# SCH_f1c200-board_2024-05-28.net
KiCad netlist of a schematic drawn in EasyEDA
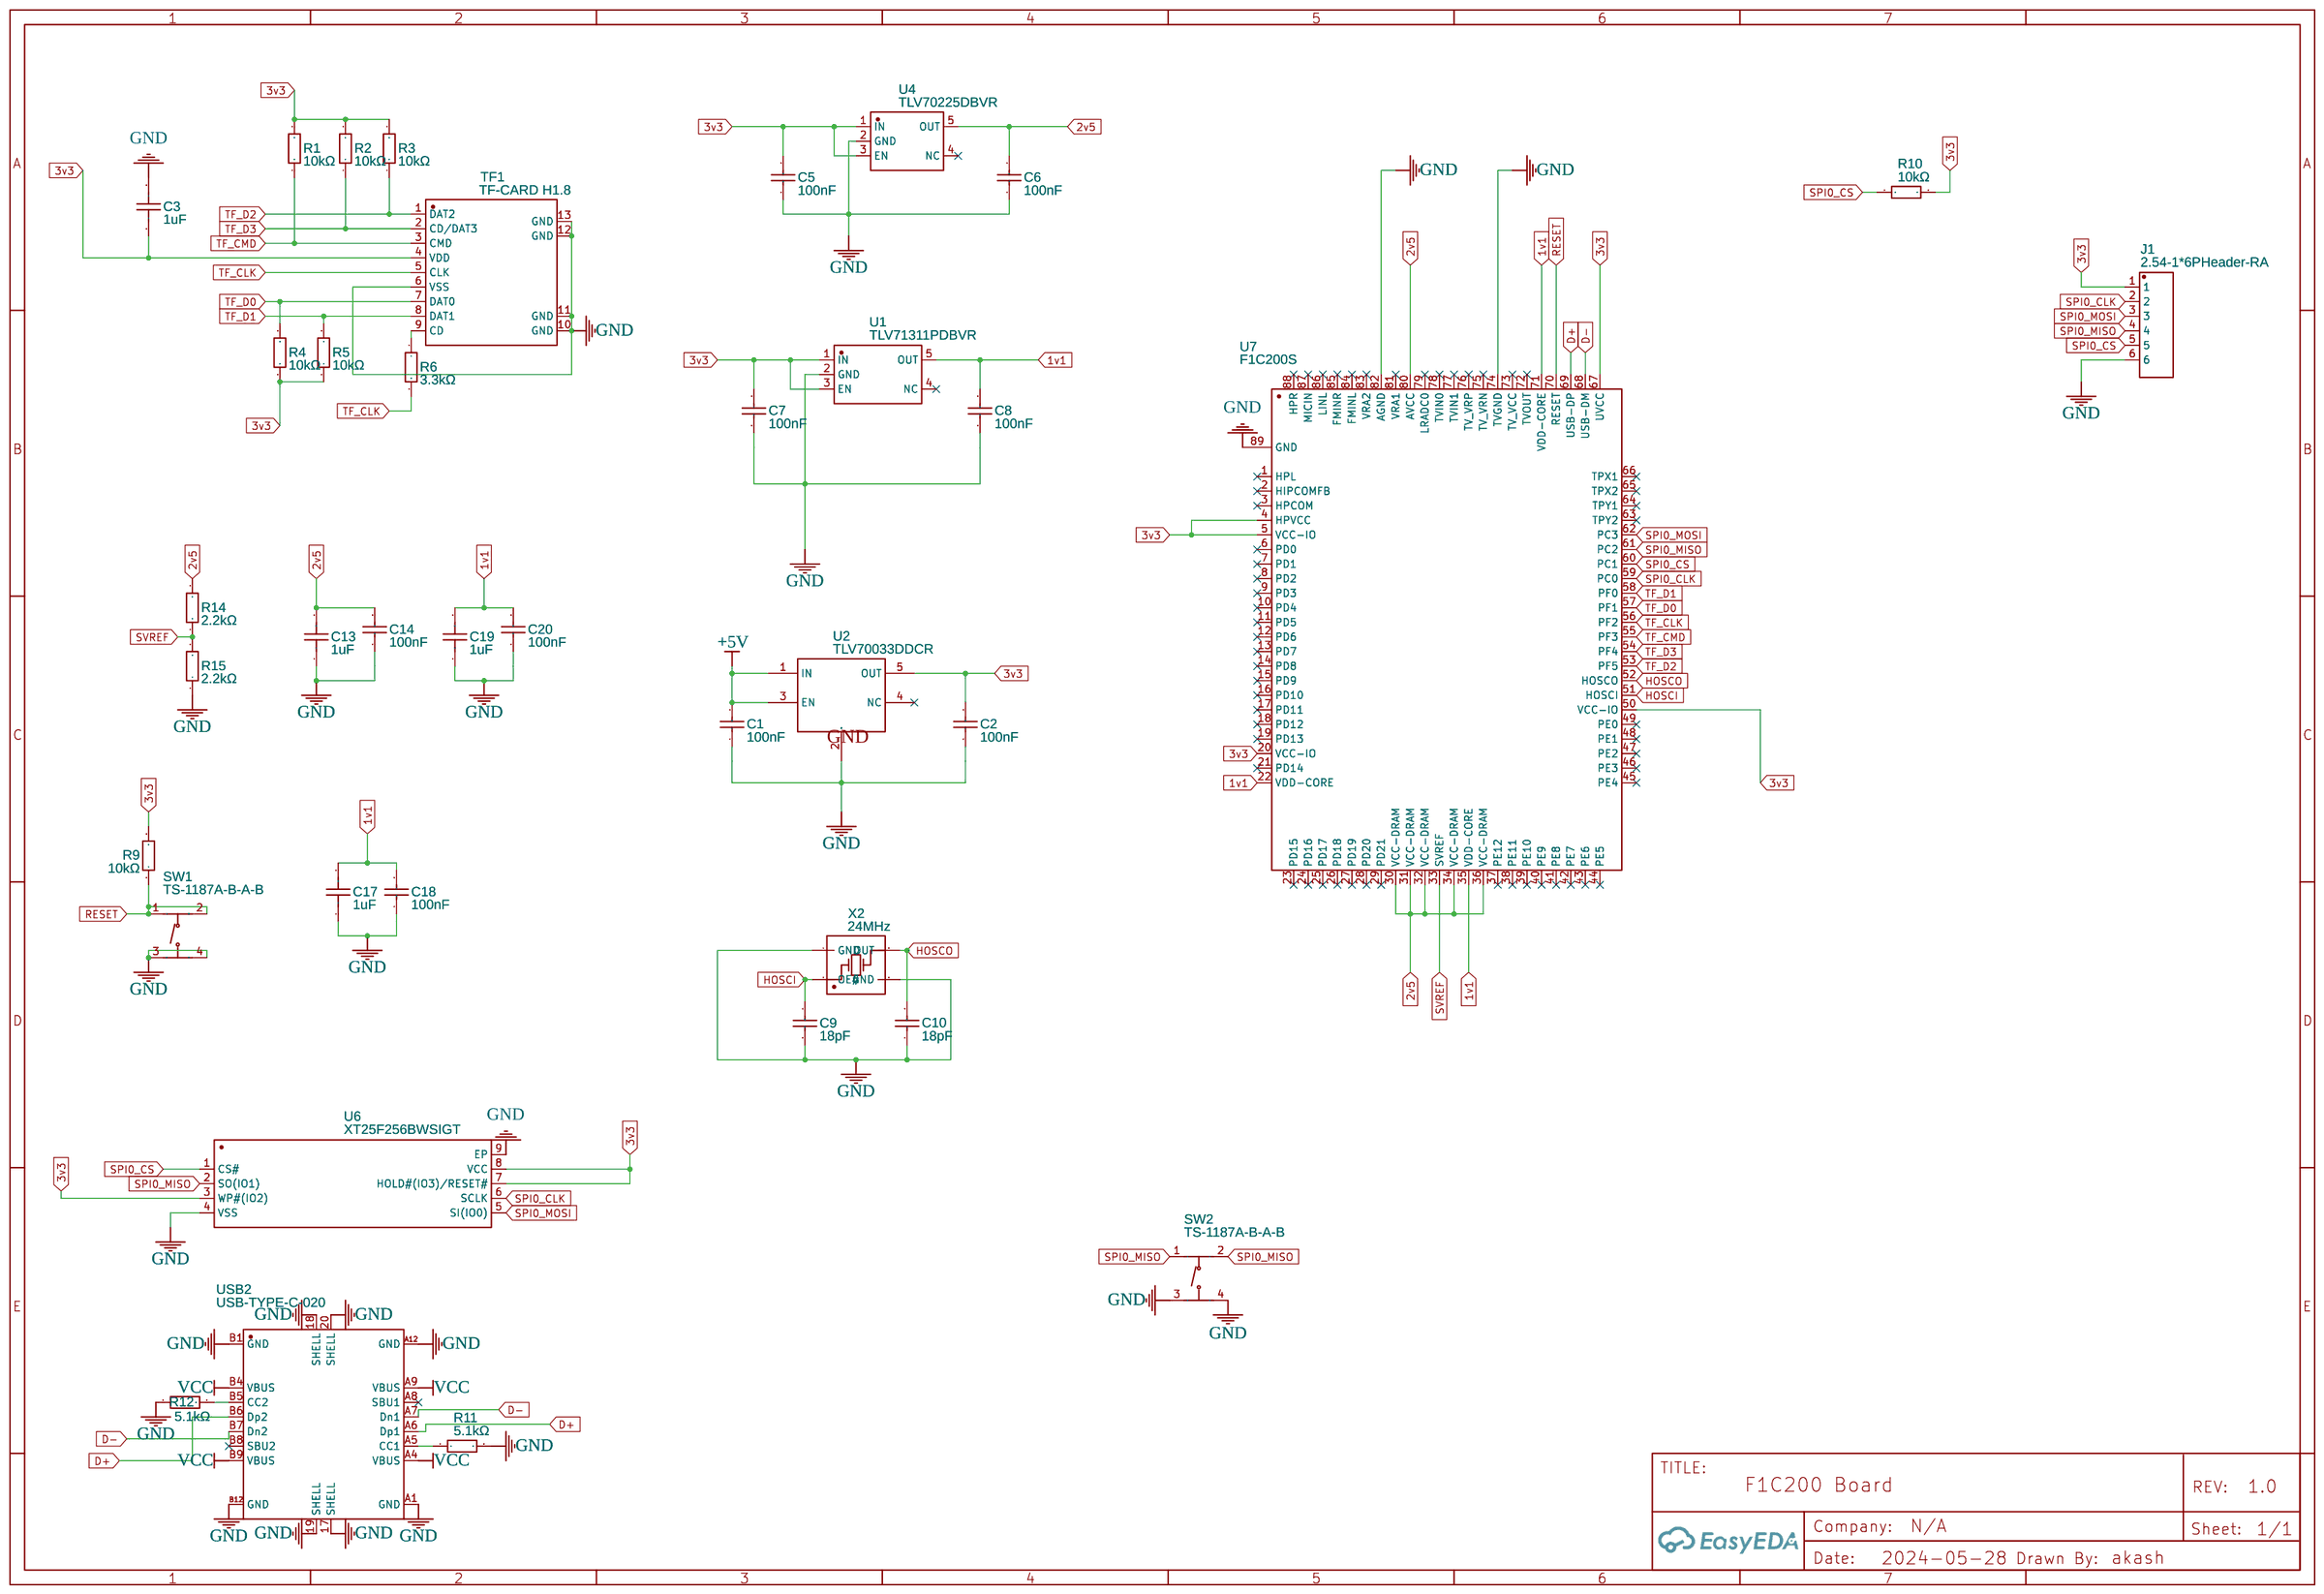
[diagram p0: schematic sheet]

(export (version "E")
  (design (tool "Eeschema 10.0.6"))
  (components
    (comp (ref "C1")
      (value "100nF")
      (fields
        (field (name "Manufacturer Part") "CL05B104KO5NNNC")
        (field (name "Manufacturer") "SAMSUNG(三星)")
      )
      (libsource (lib "") (part "CL05B104KO5NNNC"))
    )
    (comp (ref "C2")
      (value "100nF")
      (fields
        (field (name "Manufacturer Part") "CL05B104KO5NNNC")
        (field (name "Manufacturer") "SAMSUNG(三星)")
      )
      (libsource (lib "") (part "CL05B104KO5NNNC"))
    )
    (comp (ref "C3")
      (value "1uF")
      (fields
        (field (name "Manufacturer Part") "CL05A105KA5NQNC")
        (field (name "Manufacturer") "SAMSUNG(三星)")
      )
      (libsource (lib "") (part "CL05A105KA5NQNC"))
    )
    (comp (ref "C5")
      (value "100nF")
      (fields
        (field (name "Manufacturer Part") "CL05B104KO5NNNC")
        (field (name "Manufacturer") "SAMSUNG(三星)")
      )
      (libsource (lib "") (part "CL05B104KO5NNNC"))
    )
    (comp (ref "C6")
      (value "100nF")
      (fields
        (field (name "Manufacturer Part") "CL05B104KO5NNNC")
        (field (name "Manufacturer") "SAMSUNG(三星)")
      )
      (libsource (lib "") (part "CL05B104KO5NNNC"))
    )
    (comp (ref "C7")
      (value "100nF")
      (fields
        (field (name "Manufacturer Part") "CL05B104KO5NNNC")
        (field (name "Manufacturer") "SAMSUNG(三星)")
      )
      (libsource (lib "") (part "CL05B104KO5NNNC"))
    )
    (comp (ref "C8")
      (value "100nF")
      (fields
        (field (name "Manufacturer Part") "CL05B104KO5NNNC")
        (field (name "Manufacturer") "SAMSUNG(三星)")
      )
      (libsource (lib "") (part "CL05B104KO5NNNC"))
    )
    (comp (ref "C9")
      (value "18pF")
      (fields (field (name "Manufacturer Part") "0402CG180J500NT") (field (name "Manufacturer") "FH(风华)"))
      (libsource (lib "") (part "0402CG180J500NT"))
    )
    (comp (ref "C10")
      (value "18pF")
      (fields (field (name "Manufacturer Part") "0402CG180J500NT") (field (name "Manufacturer") "FH(风华)"))
      (libsource (lib "") (part "0402CG180J500NT"))
    )
    (comp (ref "C13")
      (value "1uF")
      (fields
        (field (name "Manufacturer Part") "CL05A105KA5NQNC")
        (field (name "Manufacturer") "SAMSUNG(三星)")
      )
      (libsource (lib "") (part "CL05A105KA5NQNC"))
    )
    (comp (ref "C14")
      (value "100nF")
      (fields
        (field (name "Manufacturer Part") "CL05B104KO5NNNC")
        (field (name "Manufacturer") "SAMSUNG(三星)")
      )
      (libsource (lib "") (part "CL05B104KO5NNNC"))
    )
    (comp (ref "C17")
      (value "1uF")
      (fields
        (field (name "Manufacturer Part") "CL05A105KA5NQNC")
        (field (name "Manufacturer") "SAMSUNG(三星)")
      )
      (libsource (lib "") (part "CL05A105KA5NQNC"))
    )
    (comp (ref "C18")
      (value "100nF")
      (fields
        (field (name "Manufacturer Part") "CL05B104KO5NNNC")
        (field (name "Manufacturer") "SAMSUNG(三星)")
      )
      (libsource (lib "") (part "CL05B104KO5NNNC"))
    )
    (comp (ref "C19")
      (value "1uF")
      (fields
        (field (name "Manufacturer Part") "CL05A105KA5NQNC")
        (field (name "Manufacturer") "SAMSUNG(三星)")
      )
      (libsource (lib "") (part "CL05A105KA5NQNC"))
    )
    (comp (ref "C20")
      (value "100nF")
      (fields
        (field (name "Manufacturer Part") "CL05B104KO5NNNC")
        (field (name "Manufacturer") "SAMSUNG(三星)")
      )
      (libsource (lib "") (part "CL05B104KO5NNNC"))
    )
    (comp (ref "J1")
      (value "2.54-1*6PHeader-RA")
      (fields
        (field (name "Manufacturer Part") "2.54-1*6P反弯排针")
        (field (name "Manufacturer") "BOOMELE(博穆精密)")
      )
      (libsource (lib "") (part "2.54-1*6PHeader-RA"))
    )
    (comp (ref "R1")
      (value "10kΩ")
      (fields
        (field (name "Manufacturer Part") "0603WAF1002T5E")
        (field (name "Manufacturer") "UNI-ROYAL(厚声)")
      )
      (libsource (lib "") (part "0603WAF1002T5E"))
    )
    (comp (ref "R2")
      (value "10kΩ")
      (fields
        (field (name "Manufacturer Part") "0603WAF1002T5E")
        (field (name "Manufacturer") "UNI-ROYAL(厚声)")
      )
      (libsource (lib "") (part "0603WAF1002T5E"))
    )
    (comp (ref "R3")
      (value "10kΩ")
      (fields
        (field (name "Manufacturer Part") "0603WAF1002T5E")
        (field (name "Manufacturer") "UNI-ROYAL(厚声)")
      )
      (libsource (lib "") (part "0603WAF1002T5E"))
    )
    (comp (ref "R4")
      (value "10kΩ")
      (fields
        (field (name "Manufacturer Part") "0603WAF1002T5E")
        (field (name "Manufacturer") "UNI-ROYAL(厚声)")
      )
      (libsource (lib "") (part "0603WAF1002T5E"))
    )
    (comp (ref "R5")
      (value "10kΩ")
      (fields
        (field (name "Manufacturer Part") "0603WAF1002T5E")
        (field (name "Manufacturer") "UNI-ROYAL(厚声)")
      )
      (libsource (lib "") (part "0603WAF1002T5E"))
    )
    (comp (ref "R6")
      (value "3.3kΩ")
      (fields
        (field (name "Manufacturer Part") "0603WAF3301T5E")
        (field (name "Manufacturer") "UNI-ROYAL(厚声)")
      )
      (libsource (lib "") (part "0603WAF3301T5E"))
    )
    (comp (ref "R9")
      (value "10kΩ")
      (fields
        (field (name "Manufacturer Part") "0603WAF1002T5E")
        (field (name "Manufacturer") "UNI-ROYAL(厚声)")
      )
      (libsource (lib "") (part "0603WAF1002T5E"))
    )
    (comp (ref "R10")
      (value "10kΩ")
      (fields
        (field (name "Manufacturer Part") "0603WAF1002T5E")
        (field (name "Manufacturer") "UNI-ROYAL(厚声)")
      )
      (libsource (lib "") (part "0603WAF1002T5E_1"))
    )
    (comp (ref "R11")
      (value "5.1kΩ")
      (fields
        (field (name "Manufacturer Part") "0402WGF5101TCE")
        (field (name "Manufacturer") "UNI-ROYAL(厚声)")
      )
      (libsource (lib "") (part "0402WGF5101TCE"))
    )
    (comp (ref "R12")
      (value "5.1kΩ")
      (fields
        (field (name "Manufacturer Part") "0402WGF5101TCE")
        (field (name "Manufacturer") "UNI-ROYAL(厚声)")
      )
      (libsource (lib "") (part "0402WGF5101TCE"))
    )
    (comp (ref "R14")
      (value "2.2kΩ")
      (fields
        (field (name "Manufacturer Part") "0603WAF2201T5E")
        (field (name "Manufacturer") "UNI-ROYAL(厚声)")
      )
      (libsource (lib "") (part "0603WAF2201T5E"))
    )
    (comp (ref "R15")
      (value "2.2kΩ")
      (fields
        (field (name "Manufacturer Part") "0603WAF2201T5E")
        (field (name "Manufacturer") "UNI-ROYAL(厚声)")
      )
      (libsource (lib "") (part "0603WAF2201T5E"))
    )
    (comp (ref "SW1")
      (value "TS-1187A-B-A-B")
      (fields (field (name "Manufacturer") "XKB Connectivity(中国星坤)"))
      (libsource (lib "") (part "TS-1187A-B-A-B"))
    )
    (comp (ref "SW2")
      (value "TS-1187A-B-A-B")
      (fields (field (name "Manufacturer") "XKB Connectivity(中国星坤)"))
      (libsource (lib "") (part "TS-1187A-B-A-B"))
    )
    (comp (ref "TF1")
      (value "TF-CARD H1.8")
      (fields (field (name "Manufacturer") "SHOU HAN(首韩)"))
      (libsource (lib "") (part "TF-CARD H1.8"))
    )
    (comp (ref "U1")
      (value "TLV71311PDBVR")
      (fields (field (name "Manufacturer") "TI(德州仪器)"))
      (libsource (lib "") (part "TLV71311PDBVR"))
    )
    (comp (ref "U2")
      (value "TLV70033DDCR")
      (fields (field (name "Manufacturer") "TI(德州仪器)"))
      (libsource (lib "") (part "TLV70033DDCR"))
    )
    (comp (ref "U4")
      (value "TLV70225DBVR")
      (fields (field (name "Manufacturer") "TI(德州仪器)"))
      (libsource (lib "") (part "TLV70225DBVR"))
    )
    (comp (ref "U6")
      (value "XT25F256BWSIGT")
      (fields (field (name "Manufacturer") "XTX(芯天下)"))
      (libsource (lib "") (part "XT25F256BWSIGT"))
    )
    (comp (ref "U7")
      (value "F1C200S")
      (fields (field (name "Manufacturer") "Allwinner(全志)"))
      (libsource (lib "") (part "F1C200S"))
    )
    (comp (ref "USB2")
      (value "USB-TYPE-C-020")
      (fields (field (name "Manufacturer") "DEALON(德艺隆)"))
      (libsource (lib "") (part "USB-TYPE-C-020"))
    )
    (comp (ref "X2")
      (value "24MHz")
      (fields (field (name "Manufacturer Part") "7U24000E12UCG") (field (name "Manufacturer") "SJK(晶科鑫)"))
      (libsource (lib "") (part "7U24000E12UCG"))
    )
  )
  (nets
    (net (code "1") (name "+5V") (class "Default")
      (node (ref "C1") (pin "2") (pinfunction "2_2") (pintype "input"))
      (node (ref "U2") (pin "1") (pinfunction "IN_1") (pintype "passive"))
      (node (ref "U2") (pin "3") (pinfunction "EN_3") (pintype "unspecified"))
    )
    (net (code "2") (name "1v1") (class "Default")
      (node (ref "C17") (pin "2") (pinfunction "2_2") (pintype "unspecified"))
      (node (ref "C18") (pin "2") (pinfunction "2_2") (pintype "input"))
      (node (ref "C19") (pin "2") (pinfunction "2_2") (pintype "unspecified"))
      (node (ref "C20") (pin "2") (pinfunction "2_2") (pintype "input"))
      (node (ref "C8") (pin "2") (pinfunction "2_2") (pintype "input"))
      (node (ref "U1") (pin "5") (pinfunction "OUT_5") (pintype "unspecified"))
      (node (ref "U7") (pin "22") (pinfunction "VDD-CORE_22") (pintype "unspecified"))
      (node (ref "U7") (pin "35") (pinfunction "VDD-CORE_35") (pintype "unspecified"))
      (node (ref "U7") (pin "71") (pinfunction "VDD-CORE_71") (pintype "unspecified"))
    )
    (net (code "3") (name "2v5") (class "Default")
      (node (ref "C13") (pin "2") (pinfunction "2_2") (pintype "unspecified"))
      (node (ref "C14") (pin "2") (pinfunction "2_2") (pintype "input"))
      (node (ref "C6") (pin "2") (pinfunction "2_2") (pintype "input"))
      (node (ref "R14") (pin "2") (pinfunction "2_2") (pintype "input"))
      (node (ref "U4") (pin "5") (pinfunction "OUT_5") (pintype "unspecified"))
      (node (ref "U7") (pin "30") (pinfunction "VCC-DRAM_30") (pintype "unspecified"))
      (node (ref "U7") (pin "31") (pinfunction "VCC-DRAM_31") (pintype "unspecified"))
      (node (ref "U7") (pin "32") (pinfunction "VCC-DRAM_32") (pintype "unspecified"))
      (node (ref "U7") (pin "34") (pinfunction "VCC-DRAM_34") (pintype "unspecified"))
      (node (ref "U7") (pin "36") (pinfunction "VCC-DRAM_36") (pintype "unspecified"))
      (node (ref "U7") (pin "80") (pinfunction "AVCC_80") (pintype "unspecified"))
    )
    (net (code "4") (name "3v3") (class "Default")
      (node (ref "C2") (pin "2") (pinfunction "2_2") (pintype "input"))
      (node (ref "C3") (pin "1") (pinfunction "1_1") (pintype "unspecified"))
      (node (ref "C5") (pin "2") (pinfunction "2_2") (pintype "input"))
      (node (ref "C7") (pin "2") (pinfunction "2_2") (pintype "input"))
      (node (ref "J1") (pin "1") (pinfunction "1_1") (pintype "unspecified"))
      (node (ref "R1") (pin "2") (pinfunction "2_2") (pintype "input"))
      (node (ref "R10") (pin "2") (pinfunction "2_2") (pintype "input"))
      (node (ref "R2") (pin "2") (pinfunction "2_2") (pintype "input"))
      (node (ref "R3") (pin "2") (pinfunction "2_2") (pintype "input"))
      (node (ref "R4") (pin "1") (pinfunction "1_1") (pintype "input"))
      (node (ref "R5") (pin "1") (pinfunction "1_1") (pintype "input"))
      (node (ref "R9") (pin "2") (pinfunction "2_2") (pintype "input"))
      (node (ref "TF1") (pin "4") (pinfunction "VDD_4") (pintype "unspecified"))
      (node (ref "U1") (pin "1") (pinfunction "IN_1") (pintype "unspecified"))
      (node (ref "U1") (pin "3") (pinfunction "EN_3") (pintype "unspecified"))
      (node (ref "U2") (pin "5") (pinfunction "OUT_5") (pintype "passive"))
      (node (ref "U4") (pin "1") (pinfunction "IN_1") (pintype "unspecified"))
      (node (ref "U4") (pin "3") (pinfunction "EN_3") (pintype "unspecified"))
      (node (ref "U6") (pin "3") (pinfunction "WP#(IO2)_3") (pintype "unspecified"))
      (node (ref "U6") (pin "7") (pinfunction "HOLD#(IO3)/RESET#_7") (pintype "unspecified"))
      (node (ref "U6") (pin "8") (pinfunction "VCC_8") (pintype "unspecified"))
      (node (ref "U7") (pin "20") (pinfunction "VCC-IO_20") (pintype "unspecified"))
      (node (ref "U7") (pin "4") (pinfunction "HPVCC_4") (pintype "unspecified"))
      (node (ref "U7") (pin "5") (pinfunction "VCC-IO_5") (pintype "unspecified"))
      (node (ref "U7") (pin "50") (pinfunction "VCC-IO_50") (pintype "unspecified"))
      (node (ref "U7") (pin "67") (pinfunction "UVCC_67") (pintype "unspecified"))
    )
    (net (code "5") (name "D+") (class "Default")
      (node (ref "U7") (pin "69") (pinfunction "USB-DP_69") (pintype "unspecified"))
      (node (ref "USB2") (pin "A6") (pinfunction "Dp1_A6") (pintype "unspecified"))
      (node (ref "USB2") (pin "B6") (pinfunction "Dp2_B6") (pintype "unspecified"))
    )
    (net (code "6") (name "D-") (class "Default")
      (node (ref "U7") (pin "68") (pinfunction "USB-DM_68") (pintype "unspecified"))
      (node (ref "USB2") (pin "A7") (pinfunction "Dn1_A7") (pintype "unspecified"))
      (node (ref "USB2") (pin "B7") (pinfunction "Dn2_B7") (pintype "unspecified"))
    )
    (net (code "7") (name "GND") (class "Default")
      (node (ref "C1") (pin "1") (pinfunction "1_1") (pintype "input"))
      (node (ref "C10") (pin "1") (pinfunction "1_1") (pintype "input"))
      (node (ref "C13") (pin "1") (pinfunction "1_1") (pintype "unspecified"))
      (node (ref "C14") (pin "1") (pinfunction "1_1") (pintype "input"))
      (node (ref "C17") (pin "1") (pinfunction "1_1") (pintype "unspecified"))
      (node (ref "C18") (pin "1") (pinfunction "1_1") (pintype "input"))
      (node (ref "C19") (pin "1") (pinfunction "1_1") (pintype "unspecified"))
      (node (ref "C2") (pin "1") (pinfunction "1_1") (pintype "input"))
      (node (ref "C20") (pin "1") (pinfunction "1_1") (pintype "input"))
      (node (ref "C3") (pin "2") (pinfunction "2_2") (pintype "unspecified"))
      (node (ref "C5") (pin "1") (pinfunction "1_1") (pintype "input"))
      (node (ref "C6") (pin "1") (pinfunction "1_1") (pintype "input"))
      (node (ref "C7") (pin "1") (pinfunction "1_1") (pintype "input"))
      (node (ref "C8") (pin "1") (pinfunction "1_1") (pintype "input"))
      (node (ref "C9") (pin "1") (pinfunction "1_1") (pintype "input"))
      (node (ref "J1") (pin "6") (pinfunction "6_6") (pintype "unspecified"))
      (node (ref "R11") (pin "2") (pinfunction "2_2") (pintype "input"))
      (node (ref "R12") (pin "1") (pinfunction "1_1") (pintype "input"))
      (node (ref "R15") (pin "1") (pinfunction "1_1") (pintype "input"))
      (node (ref "SW1") (pin "3") (pinfunction "C_3") (pintype "unspecified"))
      (node (ref "SW1") (pin "4") (pinfunction "D_4") (pintype "unspecified"))
      (node (ref "SW2") (pin "3") (pinfunction "C_3") (pintype "unspecified"))
      (node (ref "SW2") (pin "4") (pinfunction "D_4") (pintype "unspecified"))
      (node (ref "TF1") (pin "10") (pinfunction "GND_10") (pintype "unspecified"))
      (node (ref "TF1") (pin "11") (pinfunction "GND_11") (pintype "unspecified"))
      (node (ref "TF1") (pin "12") (pinfunction "GND_12") (pintype "unspecified"))
      (node (ref "TF1") (pin "13") (pinfunction "GND_13") (pintype "unspecified"))
      (node (ref "TF1") (pin "6") (pinfunction "VSS_6") (pintype "unspecified"))
      (node (ref "U1") (pin "2") (pinfunction "GND_2") (pintype "unspecified"))
      (node (ref "U2") (pin "2") (pinfunction "GND_2") (pintype "passive"))
      (node (ref "U4") (pin "2") (pinfunction "GND_2") (pintype "unspecified"))
      (node (ref "U6") (pin "4") (pinfunction "VSS_4") (pintype "unspecified"))
      (node (ref "U6") (pin "9") (pinfunction "EP_9") (pintype "unspecified"))
      (node (ref "U7") (pin "74") (pinfunction "TVGND_74") (pintype "unspecified"))
      (node (ref "U7") (pin "82") (pinfunction "AGND_82") (pintype "unspecified"))
      (node (ref "U7") (pin "89") (pinfunction "GND_89") (pintype "unspecified"))
      (node (ref "USB2") (pin "17") (pinfunction "SHELL_17") (pintype "unspecified"))
      (node (ref "USB2") (pin "18") (pinfunction "SHELL_18") (pintype "unspecified"))
      (node (ref "USB2") (pin "19") (pinfunction "SHELL_19") (pintype "unspecified"))
      (node (ref "USB2") (pin "20") (pinfunction "SHELL_20") (pintype "unspecified"))
      (node (ref "USB2") (pin "A1") (pinfunction "GND_A1") (pintype "unspecified"))
      (node (ref "USB2") (pin "A12") (pinfunction "GND_A12") (pintype "unspecified"))
      (node (ref "USB2") (pin "B1") (pinfunction "GND_B1") (pintype "unspecified"))
      (node (ref "USB2") (pin "B12") (pinfunction "GND_B12") (pintype "unspecified"))
      (node (ref "X2") (pin "2") (pinfunction "GND_2") (pintype "input"))
      (node (ref "X2") (pin "4") (pinfunction "GND_4") (pintype "input"))
    )
    (net (code "8") (name "HOSCI") (class "Default")
      (node (ref "C9") (pin "2") (pinfunction "2_2") (pintype "input"))
      (node (ref "U7") (pin "51") (pinfunction "HOSCI_51") (pintype "unspecified"))
      (node (ref "X2") (pin "1") (pinfunction "OE#_1") (pintype "input"))
    )
    (net (code "9") (name "HOSCO") (class "Default")
      (node (ref "C10") (pin "2") (pinfunction "2_2") (pintype "input"))
      (node (ref "U7") (pin "52") (pinfunction "HOSCO_52") (pintype "unspecified"))
      (node (ref "X2") (pin "3") (pinfunction "OUT_3") (pintype "input"))
    )
    (net (code "10") (name "Net-(TF1-CD)") (class "Default")
      (node (ref "R6") (pin "1") (pinfunction "1_1") (pintype "input"))
      (node (ref "TF1") (pin "9") (pinfunction "CD_9") (pintype "unspecified"))
    )
    (net (code "11") (name "Net-(USB2-CC1)") (class "Default")
      (node (ref "R11") (pin "1") (pinfunction "1_1") (pintype "input"))
      (node (ref "USB2") (pin "A5") (pinfunction "CC1_A5") (pintype "unspecified"))
    )
    (net (code "12") (name "Net-(USB2-CC2)") (class "Default")
      (node (ref "R12") (pin "2") (pinfunction "2_2") (pintype "input"))
      (node (ref "USB2") (pin "B5") (pinfunction "CC2_B5") (pintype "unspecified"))
    )
    (net (code "13") (name "RESET") (class "Default")
      (node (ref "R9") (pin "1") (pinfunction "1_1") (pintype "input"))
      (node (ref "SW1") (pin "1") (pinfunction "A_1") (pintype "unspecified"))
      (node (ref "SW1") (pin "2") (pinfunction "B_2") (pintype "unspecified"))
      (node (ref "U7") (pin "70") (pinfunction "RESET_70") (pintype "unspecified"))
    )
    (net (code "14") (name "SPI0_CLK") (class "Default")
      (node (ref "J1") (pin "2") (pinfunction "2_2") (pintype "unspecified"))
      (node (ref "U6") (pin "6") (pinfunction "SCLK_6") (pintype "unspecified"))
      (node (ref "U7") (pin "59") (pinfunction "PC0_59") (pintype "unspecified"))
    )
    (net (code "15") (name "SPI0_CS") (class "Default")
      (node (ref "J1") (pin "5") (pinfunction "5_5") (pintype "unspecified"))
      (node (ref "R10") (pin "1") (pinfunction "1_1") (pintype "input"))
      (node (ref "U6") (pin "1") (pinfunction "CS#_1") (pintype "unspecified"))
      (node (ref "U7") (pin "60") (pinfunction "PC1_60") (pintype "unspecified"))
    )
    (net (code "16") (name "SPI0_MISO") (class "Default")
      (node (ref "J1") (pin "4") (pinfunction "4_4") (pintype "unspecified"))
      (node (ref "SW2") (pin "1") (pinfunction "A_1") (pintype "unspecified"))
      (node (ref "SW2") (pin "2") (pinfunction "B_2") (pintype "unspecified"))
      (node (ref "U6") (pin "2") (pinfunction "SO(IO1)_2") (pintype "unspecified"))
      (node (ref "U7") (pin "61") (pinfunction "PC2_61") (pintype "unspecified"))
    )
    (net (code "17") (name "SPI0_MOSI") (class "Default")
      (node (ref "J1") (pin "3") (pinfunction "3_3") (pintype "unspecified"))
      (node (ref "U6") (pin "5") (pinfunction "SI(IO0)_5") (pintype "unspecified"))
      (node (ref "U7") (pin "62") (pinfunction "PC3_62") (pintype "unspecified"))
    )
    (net (code "18") (name "SVREF") (class "Default")
      (node (ref "R14") (pin "1") (pinfunction "1_1") (pintype "input"))
      (node (ref "R15") (pin "2") (pinfunction "2_2") (pintype "input"))
      (node (ref "U7") (pin "33") (pinfunction "SVREF_33") (pintype "unspecified"))
    )
    (net (code "19") (name "TF_CLK") (class "Default")
      (node (ref "R6") (pin "2") (pinfunction "2_2") (pintype "input"))
      (node (ref "TF1") (pin "5") (pinfunction "CLK_5") (pintype "unspecified"))
      (node (ref "U7") (pin "56") (pinfunction "PF2_56") (pintype "unspecified"))
    )
    (net (code "20") (name "TF_CMD") (class "Default")
      (node (ref "R1") (pin "1") (pinfunction "1_1") (pintype "input"))
      (node (ref "TF1") (pin "3") (pinfunction "CMD_3") (pintype "unspecified"))
      (node (ref "U7") (pin "55") (pinfunction "PF3_55") (pintype "unspecified"))
    )
    (net (code "21") (name "TF_D0") (class "Default")
      (node (ref "R4") (pin "2") (pinfunction "2_2") (pintype "input"))
      (node (ref "TF1") (pin "7") (pinfunction "DAT0_7") (pintype "unspecified"))
      (node (ref "U7") (pin "57") (pinfunction "PF1_57") (pintype "unspecified"))
    )
    (net (code "22") (name "TF_D1") (class "Default")
      (node (ref "R5") (pin "2") (pinfunction "2_2") (pintype "input"))
      (node (ref "TF1") (pin "8") (pinfunction "DAT1_8") (pintype "unspecified"))
      (node (ref "U7") (pin "58") (pinfunction "PF0_58") (pintype "unspecified"))
    )
    (net (code "23") (name "TF_D2") (class "Default")
      (node (ref "R3") (pin "1") (pinfunction "1_1") (pintype "input"))
      (node (ref "TF1") (pin "1") (pinfunction "DAT2_1") (pintype "unspecified"))
      (node (ref "U7") (pin "53") (pinfunction "PF5_53") (pintype "unspecified"))
    )
    (net (code "24") (name "TF_D3") (class "Default")
      (node (ref "R2") (pin "1") (pinfunction "1_1") (pintype "input"))
      (node (ref "TF1") (pin "2") (pinfunction "CD/DAT3_2") (pintype "unspecified"))
      (node (ref "U7") (pin "54") (pinfunction "PF4_54") (pintype "unspecified"))
    )
    (net (code "25") (name "VCC") (class "Default")
      (node (ref "USB2") (pin "A4") (pinfunction "VBUS_A4") (pintype "unspecified"))
      (node (ref "USB2") (pin "A9") (pinfunction "VBUS_A9") (pintype "unspecified"))
      (node (ref "USB2") (pin "B4") (pinfunction "VBUS_B4") (pintype "unspecified"))
      (node (ref "USB2") (pin "B9") (pinfunction "VBUS_B9") (pintype "unspecified"))
    )
    (net (code "26") (name "unconnected-(U1-NC-Pad4)") (class "Default")
      (node (ref "U1") (pin "4") (pinfunction "NC_4") (pintype "unspecified+no_connect"))
    )
    (net (code "27") (name "unconnected-(U2-NC-Pad4)") (class "Default")
      (node (ref "U2") (pin "4") (pinfunction "NC_4") (pintype "unspecified+no_connect"))
    )
    (net (code "28") (name "unconnected-(U4-NC-Pad4)") (class "Default")
      (node (ref "U4") (pin "4") (pinfunction "NC_4") (pintype "unspecified+no_connect"))
    )
    (net (code "29") (name "unconnected-(U7-FMINL-Pad84)") (class "Default")
      (node (ref "U7") (pin "84") (pinfunction "FMINL_84") (pintype "unspecified+no_connect"))
    )
    (net (code "30") (name "unconnected-(U7-FMINR-Pad85)") (class "Default")
      (node (ref "U7") (pin "85") (pinfunction "FMINR_85") (pintype "unspecified+no_connect"))
    )
    (net (code "31") (name "unconnected-(U7-HIPCOMFB-Pad2)") (class "Default")
      (node (ref "U7") (pin "2") (pinfunction "HIPCOMFB_2") (pintype "unspecified+no_connect"))
    )
    (net (code "32") (name "unconnected-(U7-HPCOM-Pad3)") (class "Default")
      (node (ref "U7") (pin "3") (pinfunction "HPCOM_3") (pintype "unspecified+no_connect"))
    )
    (net (code "33") (name "unconnected-(U7-HPL-Pad1)") (class "Default")
      (node (ref "U7") (pin "1") (pinfunction "HPL_1") (pintype "unspecified+no_connect"))
    )
    (net (code "34") (name "unconnected-(U7-HPR-Pad88)") (class "Default")
      (node (ref "U7") (pin "88") (pinfunction "HPR_88") (pintype "unspecified+no_connect"))
    )
    (net (code "35") (name "unconnected-(U7-LINL-Pad86)") (class "Default")
      (node (ref "U7") (pin "86") (pinfunction "LINL_86") (pintype "unspecified+no_connect"))
    )
    (net (code "36") (name "unconnected-(U7-LRADC0-Pad79)") (class "Default")
      (node (ref "U7") (pin "79") (pinfunction "LRADC0_79") (pintype "unspecified+no_connect"))
    )
    (net (code "37") (name "unconnected-(U7-MICIN-Pad87)") (class "Default")
      (node (ref "U7") (pin "87") (pinfunction "MICIN_87") (pintype "unspecified+no_connect"))
    )
    (net (code "38") (name "unconnected-(U7-PD0-Pad6)") (class "Default")
      (node (ref "U7") (pin "6") (pinfunction "PD0_6") (pintype "unspecified+no_connect"))
    )
    (net (code "39") (name "unconnected-(U7-PD1-Pad7)") (class "Default")
      (node (ref "U7") (pin "7") (pinfunction "PD1_7") (pintype "unspecified+no_connect"))
    )
    (net (code "40") (name "unconnected-(U7-PD2-Pad8)") (class "Default")
      (node (ref "U7") (pin "8") (pinfunction "PD2_8") (pintype "unspecified+no_connect"))
    )
    (net (code "41") (name "unconnected-(U7-PD3-Pad9)") (class "Default")
      (node (ref "U7") (pin "9") (pinfunction "PD3_9") (pintype "unspecified+no_connect"))
    )
    (net (code "42") (name "unconnected-(U7-PD4-Pad10)") (class "Default")
      (node (ref "U7") (pin "10") (pinfunction "PD4_10") (pintype "unspecified+no_connect"))
    )
    (net (code "43") (name "unconnected-(U7-PD5-Pad11)") (class "Default")
      (node (ref "U7") (pin "11") (pinfunction "PD5_11") (pintype "unspecified+no_connect"))
    )
    (net (code "44") (name "unconnected-(U7-PD6-Pad12)") (class "Default")
      (node (ref "U7") (pin "12") (pinfunction "PD6_12") (pintype "unspecified+no_connect"))
    )
    (net (code "45") (name "unconnected-(U7-PD7-Pad13)") (class "Default")
      (node (ref "U7") (pin "13") (pinfunction "PD7_13") (pintype "unspecified+no_connect"))
    )
    (net (code "46") (name "unconnected-(U7-PD8-Pad14)") (class "Default")
      (node (ref "U7") (pin "14") (pinfunction "PD8_14") (pintype "unspecified+no_connect"))
    )
    (net (code "47") (name "unconnected-(U7-PD9-Pad15)") (class "Default")
      (node (ref "U7") (pin "15") (pinfunction "PD9_15") (pintype "unspecified+no_connect"))
    )
    (net (code "48") (name "unconnected-(U7-PD10-Pad16)") (class "Default")
      (node (ref "U7") (pin "16") (pinfunction "PD10_16") (pintype "unspecified+no_connect"))
    )
    (net (code "49") (name "unconnected-(U7-PD11-Pad17)") (class "Default")
      (node (ref "U7") (pin "17") (pinfunction "PD11_17") (pintype "unspecified+no_connect"))
    )
    (net (code "50") (name "unconnected-(U7-PD12-Pad18)") (class "Default")
      (node (ref "U7") (pin "18") (pinfunction "PD12_18") (pintype "unspecified+no_connect"))
    )
    (net (code "51") (name "unconnected-(U7-PD13-Pad19)") (class "Default")
      (node (ref "U7") (pin "19") (pinfunction "PD13_19") (pintype "unspecified+no_connect"))
    )
    (net (code "52") (name "unconnected-(U7-PD14-Pad21)") (class "Default")
      (node (ref "U7") (pin "21") (pinfunction "PD14_21") (pintype "unspecified+no_connect"))
    )
    (net (code "53") (name "unconnected-(U7-PD15-Pad23)") (class "Default")
      (node (ref "U7") (pin "23") (pinfunction "PD15_23") (pintype "unspecified+no_connect"))
    )
    (net (code "54") (name "unconnected-(U7-PD16-Pad24)") (class "Default")
      (node (ref "U7") (pin "24") (pinfunction "PD16_24") (pintype "unspecified+no_connect"))
    )
    (net (code "55") (name "unconnected-(U7-PD17-Pad25)") (class "Default")
      (node (ref "U7") (pin "25") (pinfunction "PD17_25") (pintype "unspecified+no_connect"))
    )
    (net (code "56") (name "unconnected-(U7-PD18-Pad26)") (class "Default")
      (node (ref "U7") (pin "26") (pinfunction "PD18_26") (pintype "unspecified+no_connect"))
    )
    (net (code "57") (name "unconnected-(U7-PD19-Pad27)") (class "Default")
      (node (ref "U7") (pin "27") (pinfunction "PD19_27") (pintype "unspecified+no_connect"))
    )
    (net (code "58") (name "unconnected-(U7-PD20-Pad28)") (class "Default")
      (node (ref "U7") (pin "28") (pinfunction "PD20_28") (pintype "unspecified+no_connect"))
    )
    (net (code "59") (name "unconnected-(U7-PD21-Pad29)") (class "Default")
      (node (ref "U7") (pin "29") (pinfunction "PD21_29") (pintype "unspecified+no_connect"))
    )
    (net (code "60") (name "unconnected-(U7-PE0-Pad49)") (class "Default")
      (node (ref "U7") (pin "49") (pinfunction "PE0_49") (pintype "unspecified+no_connect"))
    )
    (net (code "61") (name "unconnected-(U7-PE1-Pad48)") (class "Default")
      (node (ref "U7") (pin "48") (pinfunction "PE1_48") (pintype "unspecified+no_connect"))
    )
    (net (code "62") (name "unconnected-(U7-PE2-Pad47)") (class "Default")
      (node (ref "U7") (pin "47") (pinfunction "PE2_47") (pintype "unspecified+no_connect"))
    )
    (net (code "63") (name "unconnected-(U7-PE3-Pad46)") (class "Default")
      (node (ref "U7") (pin "46") (pinfunction "PE3_46") (pintype "unspecified+no_connect"))
    )
    (net (code "64") (name "unconnected-(U7-PE4-Pad45)") (class "Default")
      (node (ref "U7") (pin "45") (pinfunction "PE4_45") (pintype "unspecified+no_connect"))
    )
    (net (code "65") (name "unconnected-(U7-PE5-Pad44)") (class "Default")
      (node (ref "U7") (pin "44") (pinfunction "PE5_44") (pintype "unspecified+no_connect"))
    )
    (net (code "66") (name "unconnected-(U7-PE6-Pad43)") (class "Default")
      (node (ref "U7") (pin "43") (pinfunction "PE6_43") (pintype "unspecified+no_connect"))
    )
    (net (code "67") (name "unconnected-(U7-PE7-Pad42)") (class "Default")
      (node (ref "U7") (pin "42") (pinfunction "PE7_42") (pintype "unspecified+no_connect"))
    )
    (net (code "68") (name "unconnected-(U7-PE8-Pad41)") (class "Default")
      (node (ref "U7") (pin "41") (pinfunction "PE8_41") (pintype "unspecified+no_connect"))
    )
    (net (code "69") (name "unconnected-(U7-PE9-Pad40)") (class "Default")
      (node (ref "U7") (pin "40") (pinfunction "PE9_40") (pintype "unspecified+no_connect"))
    )
    (net (code "70") (name "unconnected-(U7-PE10-Pad39)") (class "Default")
      (node (ref "U7") (pin "39") (pinfunction "PE10_39") (pintype "unspecified+no_connect"))
    )
    (net (code "71") (name "unconnected-(U7-PE11-Pad38)") (class "Default")
      (node (ref "U7") (pin "38") (pinfunction "PE11_38") (pintype "unspecified+no_connect"))
    )
    (net (code "72") (name "unconnected-(U7-PE12-Pad37)") (class "Default")
      (node (ref "U7") (pin "37") (pinfunction "PE12_37") (pintype "unspecified+no_connect"))
    )
    (net (code "73") (name "unconnected-(U7-TPX1-Pad66)") (class "Default")
      (node (ref "U7") (pin "66") (pinfunction "TPX1_66") (pintype "unspecified+no_connect"))
    )
    (net (code "74") (name "unconnected-(U7-TPX2-Pad65)") (class "Default")
      (node (ref "U7") (pin "65") (pinfunction "TPX2_65") (pintype "unspecified+no_connect"))
    )
    (net (code "75") (name "unconnected-(U7-TPY1-Pad64)") (class "Default")
      (node (ref "U7") (pin "64") (pinfunction "TPY1_64") (pintype "unspecified+no_connect"))
    )
    (net (code "76") (name "unconnected-(U7-TPY2-Pad63)") (class "Default")
      (node (ref "U7") (pin "63") (pinfunction "TPY2_63") (pintype "unspecified+no_connect"))
    )
    (net (code "77") (name "unconnected-(U7-TVIN0-Pad78)") (class "Default")
      (node (ref "U7") (pin "78") (pinfunction "TVIN0_78") (pintype "unspecified+no_connect"))
    )
    (net (code "78") (name "unconnected-(U7-TVIN1-Pad77)") (class "Default")
      (node (ref "U7") (pin "77") (pinfunction "TVIN1_77") (pintype "unspecified+no_connect"))
    )
    (net (code "79") (name "unconnected-(U7-TVOUT-Pad72)") (class "Default")
      (node (ref "U7") (pin "72") (pinfunction "TVOUT_72") (pintype "unspecified+no_connect"))
    )
    (net (code "80") (name "unconnected-(U7-TV_VCC-Pad73)") (class "Default")
      (node (ref "U7") (pin "73") (pinfunction "TV_VCC_73") (pintype "unspecified+no_connect"))
    )
    (net (code "81") (name "unconnected-(U7-TV_VRN-Pad75)") (class "Default")
      (node (ref "U7") (pin "75") (pinfunction "TV_VRN_75") (pintype "unspecified+no_connect"))
    )
    (net (code "82") (name "unconnected-(U7-TV_VRP-Pad76)") (class "Default")
      (node (ref "U7") (pin "76") (pinfunction "TV_VRP_76") (pintype "unspecified+no_connect"))
    )
    (net (code "83") (name "unconnected-(U7-VRA1-Pad81)") (class "Default")
      (node (ref "U7") (pin "81") (pinfunction "VRA1_81") (pintype "unspecified+no_connect"))
    )
    (net (code "84") (name "unconnected-(U7-VRA2-Pad83)") (class "Default")
      (node (ref "U7") (pin "83") (pinfunction "VRA2_83") (pintype "unspecified+no_connect"))
    )
    (net (code "85") (name "unconnected-(USB2-SBU1-PadA8)") (class "Default")
      (node (ref "USB2") (pin "A8") (pinfunction "SBU1_A8") (pintype "unspecified+no_connect"))
    )
    (net (code "86") (name "unconnected-(USB2-SBU2-PadB8)") (class "Default")
      (node (ref "USB2") (pin "B8") (pinfunction "SBU2_B8") (pintype "unspecified+no_connect"))
    )
  )
)
